# Esquematico_DIY.net
KiCad netlist of a schematic drawn in Altium Designer
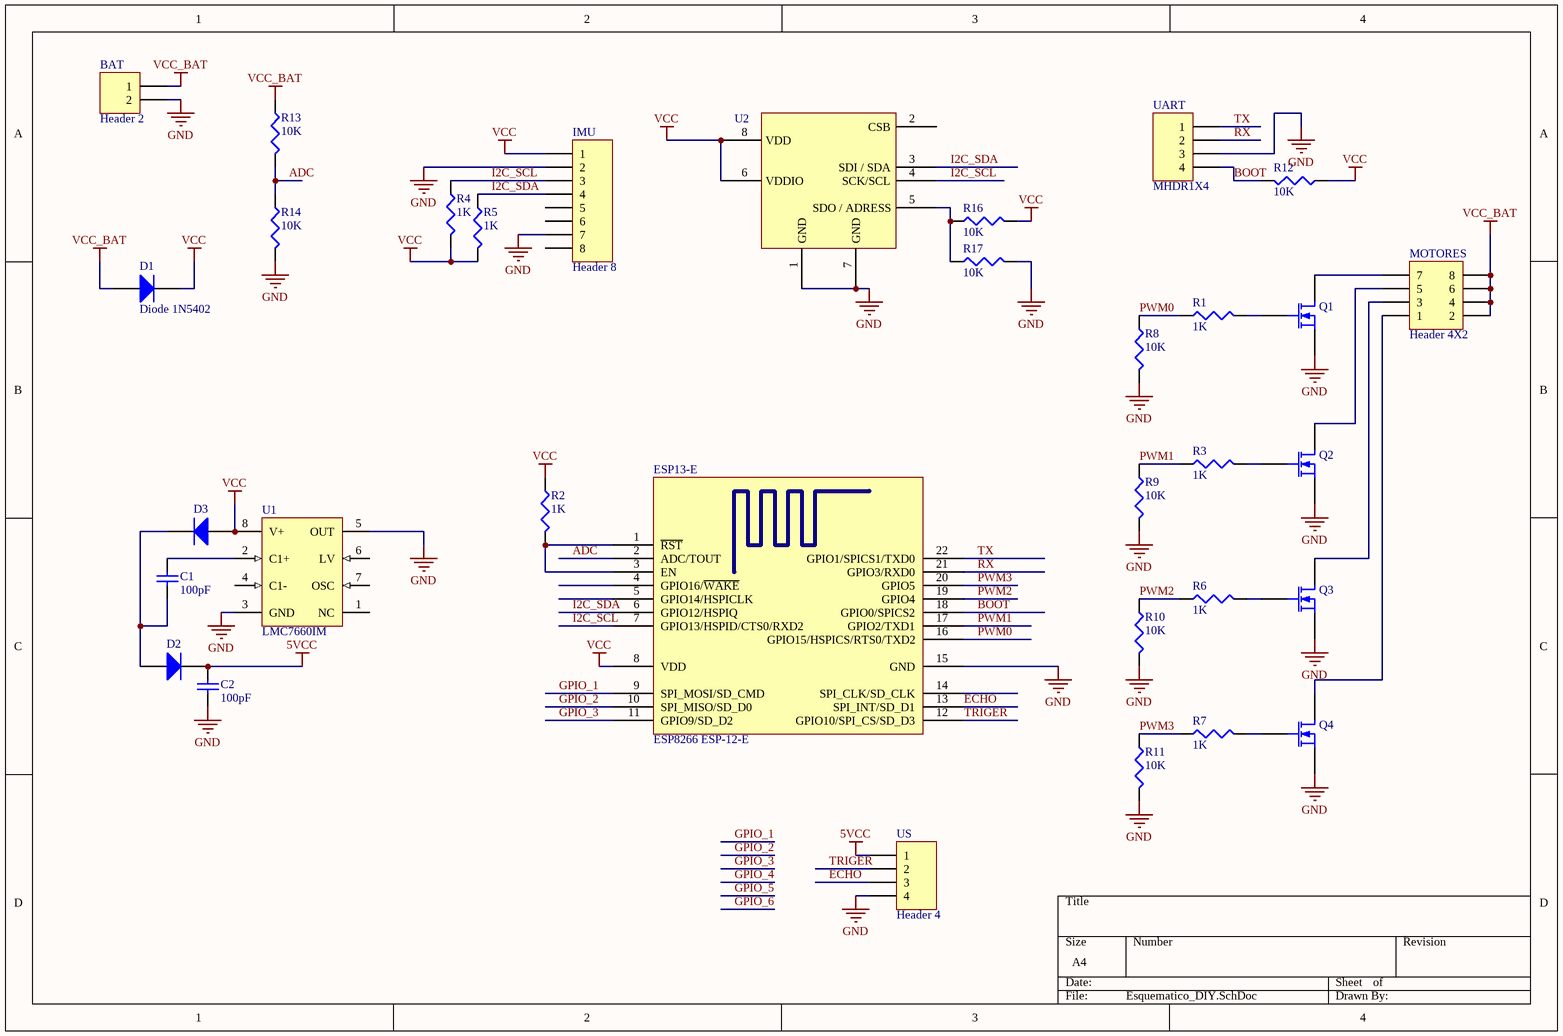
[diagram p0: Esquematico_DIY.SchDoc]

(export (version "E")
  (design (tool "Eeschema 10.0.6"))
  (components
    (comp (ref "BAT")
      (value "Header 2")
      (footprint "Miscellaneous Connectors:MHDR1X2")
      (description "Header, 2-Pin")
      (fields (field (name "PUBLISHER") "Altium Limited"))
      (libsource (lib "Miscellaneous Connectors") (part "Header 2"))
    )
    (comp (ref "C1")
      (value "100pF")
      (footprint "Miscellaneous Devices:C0805")
      (description "Capacitor")
      (fields (field (name "Comment") "Cap") (field (name "PUBLISHER") "Altium Limited"))
      (libsource (lib "Miscellaneous Devices") (part "Cap"))
    )
    (comp (ref "C2")
      (value "100pF")
      (footprint "Miscellaneous Devices:C0805")
      (description "Capacitor")
      (fields (field (name "Comment") "Cap") (field (name "PUBLISHER") "Altium Limited"))
      (libsource (lib "Miscellaneous Devices") (part "Cap"))
    )
    (comp (ref "D1")
      (value "Diode 1N5402")
      (footprint "DSO-C2/X2.3")
      (description "3 Amp General Purpose Rectifier")
      (fields (field (name "PUBLISHER") "Altium Limited"))
      (libsource (lib "Miscellaneous Devices") (part "Diode 1N5402"))
    )
    (comp (ref "D2")
      (value "Diode 1N5402")
      (footprint "DSO-C2/Z6.7")
      (description "3 Amp General Purpose Rectifier")
      (fields (field (name "PUBLISHER") "Altium Limited"))
      (libsource (lib "Miscellaneous Devices") (part "Diode 1N5402"))
    )
    (comp (ref "D3")
      (value "Diode 1N5402")
      (footprint "DSO-C2/Z6.7")
      (description "3 Amp General Purpose Rectifier")
      (fields (field (name "PUBLISHER") "Altium Limited"))
      (libsource (lib "Miscellaneous Devices") (part "Diode 1N5402"))
    )
    (comp (ref "ESP13-E")
      (value "ESP8266 ESP-12-E")
      (footprint "ESP8266:ESP8266 ESP-12-E B")
      (libsource (lib "ESP8266") (part "ESP8266 ESP-12-E"))
    )
    (comp (ref "IMU")
      (value "Header 8")
      (footprint "HDR1X8")
      (description "Header, 8-Pin")
      (fields (field (name "PUBLISHER") "Altium Limited"))
      (libsource (lib "Miscellaneous Connectors") (part "Header 8"))
    )
    (comp (ref "MOTORES")
      (value "Header 4X2")
      (footprint "HDR2X4")
      (description "Header, 4-Pin, Dual row")
      (fields (field (name "PUBLISHER") "Altium Limited"))
      (libsource (lib "Miscellaneous Connectors") (part "Header 4X2"))
    )
    (comp (ref "Q1")
      (value "MOSFET-N")
      (footprint "PBL - SMD Packages:SOT23-3")
      (description "N-Channel MOSFET")
      (fields (field (name "PUBLISHER") "Altium Limited"))
      (libsource (lib "Miscellaneous Devices") (part "MOSFET-N"))
    )
    (comp (ref "Q2")
      (value "MOSFET-N")
      (footprint "PBL - SMD Packages:SOT23-3")
      (description "N-Channel MOSFET")
      (fields (field (name "PUBLISHER") "Altium Limited"))
      (libsource (lib "Miscellaneous Devices") (part "MOSFET-N"))
    )
    (comp (ref "Q3")
      (value "MOSFET-N")
      (footprint "PBL - SMD Packages:SOT23-3")
      (description "N-Channel MOSFET")
      (fields (field (name "PUBLISHER") "Altium Limited"))
      (libsource (lib "Miscellaneous Devices") (part "MOSFET-N"))
    )
    (comp (ref "Q4")
      (value "MOSFET-N")
      (footprint "PBL - SMD Packages:SOT23-3")
      (description "N-Channel MOSFET")
      (fields (field (name "PUBLISHER") "Altium Limited"))
      (libsource (lib "Miscellaneous Devices") (part "MOSFET-N"))
    )
    (comp (ref "R1")
      (value "1K")
      (footprint "C0805")
      (description "Resistor")
      (fields (field (name "Comment") "Res3") (field (name "PUBLISHER") "Altium Limited"))
      (libsource (lib "Miscellaneous Devices") (part "Res3"))
    )
    (comp (ref "R2")
      (value "1K")
      (footprint "C0805")
      (description "Resistor")
      (fields (field (name "Comment") "Res3") (field (name "PUBLISHER") "Altium Limited"))
      (libsource (lib "Miscellaneous Devices") (part "Res3"))
    )
    (comp (ref "R3")
      (value "1K")
      (footprint "C0805")
      (description "Resistor")
      (fields (field (name "Comment") "Res3") (field (name "PUBLISHER") "Altium Limited"))
      (libsource (lib "Miscellaneous Devices") (part "Res3"))
    )
    (comp (ref "R4")
      (value "1K")
      (footprint "C1206")
      (description "Resistor")
      (fields (field (name "Comment") "Res3") (field (name "PUBLISHER") "Altium Limited"))
      (libsource (lib "Miscellaneous Devices") (part "Res3"))
    )
    (comp (ref "R5")
      (value "1K")
      (footprint "C1206")
      (description "Resistor")
      (fields (field (name "Comment") "Res3") (field (name "PUBLISHER") "Altium Limited"))
      (libsource (lib "Miscellaneous Devices") (part "Res3"))
    )
    (comp (ref "R6")
      (value "1K")
      (footprint "C0805")
      (description "Resistor")
      (fields (field (name "Comment") "Res3") (field (name "PUBLISHER") "Altium Limited"))
      (libsource (lib "Miscellaneous Devices") (part "Res3"))
    )
    (comp (ref "R7")
      (value "1K")
      (footprint "C0805")
      (description "Resistor")
      (fields (field (name "Comment") "Res3") (field (name "PUBLISHER") "Altium Limited"))
      (libsource (lib "Miscellaneous Devices") (part "Res3"))
    )
    (comp (ref "R8")
      (value "10K")
      (footprint "C0805")
      (description "Resistor")
      (fields (field (name "Comment") "Res3") (field (name "PUBLISHER") "Altium Limited"))
      (libsource (lib "Miscellaneous Devices") (part "Res3"))
    )
    (comp (ref "R9")
      (value "10K")
      (footprint "C0805")
      (description "Resistor")
      (fields (field (name "Comment") "Res3") (field (name "PUBLISHER") "Altium Limited"))
      (libsource (lib "Miscellaneous Devices") (part "Res3"))
    )
    (comp (ref "R10")
      (value "10K")
      (footprint "C0805")
      (description "Resistor")
      (fields (field (name "Comment") "Res3") (field (name "PUBLISHER") "Altium Limited"))
      (libsource (lib "Miscellaneous Devices") (part "Res3"))
    )
    (comp (ref "R11")
      (value "10K")
      (footprint "C0805")
      (description "Resistor")
      (fields (field (name "Comment") "Res3") (field (name "PUBLISHER") "Altium Limited"))
      (libsource (lib "Miscellaneous Devices") (part "Res3"))
    )
    (comp (ref "R12")
      (value "10K")
      (footprint "C1206")
      (description "Resistor")
      (fields (field (name "Comment") "Res3") (field (name "PUBLISHER") "Altium Limited"))
      (libsource (lib "Miscellaneous Devices") (part "Res3"))
    )
    (comp (ref "R13")
      (value "10K")
      (footprint "C0805")
      (description "Resistor")
      (fields (field (name "Comment") "Res3") (field (name "PUBLISHER") "Altium Limited"))
      (libsource (lib "Miscellaneous Devices") (part "Res3"))
    )
    (comp (ref "R14")
      (value "10K")
      (footprint "C0805")
      (description "Resistor")
      (fields (field (name "Comment") "Res3") (field (name "PUBLISHER") "Altium Limited"))
      (libsource (lib "Miscellaneous Devices") (part "Res3"))
    )
    (comp (ref "R16")
      (value "10K")
      (footprint "C0805")
      (description "Resistor")
      (fields (field (name "Comment") "Res3") (field (name "PUBLISHER") "Altium Limited"))
      (libsource (lib "Miscellaneous Devices") (part "Res3"))
    )
    (comp (ref "R17")
      (value "10K")
      (footprint "C0805")
      (description "Resistor")
      (fields (field (name "Comment") "Res3") (field (name "PUBLISHER") "Altium Limited"))
      (libsource (lib "Miscellaneous Devices") (part "Res3"))
    )
    (comp (ref "U1")
      (value "LMC7660IM")
      (footprint "M08A_N")
      (description "Switched Capacitor Voltage Converter, 8-pin Narrow SOIC")
      (fields
        (field (name "MANUFACTURER") "National Semiconductor")
        (field (name "PUBLISHER") "Altium Limited")
      )
      (libsource (lib "NSC Switch Caps") (part "LMC7660IM"))
    )
    (comp (ref "U2")
      (value "BMP280")
      (footprint "LGA-8_BMP280(Primary)")
      (description "Barometro")
      (libsource (lib "BMP280") (part "BMP280"))
    )
    (comp (ref "UART")
      (value "MHDR1X4")
      (footprint "MHDR1X4")
      (description "Header, 4-Pin")
      (fields (field (name "PUBLISHER") "Altium Limited"))
      (libsource (lib "Miscellaneous Connectors") (part "MHDR1X4"))
    )
    (comp (ref "US")
      (value "Header 4")
      (footprint "HDR1X4")
      (description "Header, 4-Pin")
      (fields (field (name "PUBLISHER") "Altium Limited"))
      (libsource (lib "Miscellaneous Connectors") (part "Header 4"))
    )
  )
  (nets
    (net (code "1") (name "/ADC") (class "Default")
      (node (ref "ESP13-E") (pin "2") (pinfunction "ADC/TOUT_2") (pintype "passive"))
      (node (ref "R13") (pin "2") (pinfunction "2_2") (pintype "passive"))
      (node (ref "R14") (pin "1") (pinfunction "1_1") (pintype "passive"))
    )
    (net (code "2") (name "/BOOT") (class "Default")
      (node (ref "ESP13-E") (pin "18") (pinfunction "GPIO0/SPICS2_18") (pintype "passive"))
      (node (ref "R12") (pin "2") (pinfunction "2_2") (pintype "passive"))
      (node (ref "UART") (pin "4") (pinfunction "4_4") (pintype "passive"))
    )
    (net (code "3") (name "/ECHO") (class "Default")
      (node (ref "ESP13-E") (pin "13") (pinfunction "SPI_INT/SD_D1_13") (pintype "passive"))
      (node (ref "US") (pin "3") (pinfunction "3_3") (pintype "passive"))
    )
    (net (code "4") (name "/GPIO_1") (class "Default")
      (node (ref "ESP13-E") (pin "9") (pinfunction "SPI_MOSI/SD_CMD_9") (pintype "passive"))
    )
    (net (code "5") (name "/GPIO_2") (class "Default")
      (node (ref "ESP13-E") (pin "10") (pinfunction "SPI_MISO/SD_D0_10") (pintype "passive"))
    )
    (net (code "6") (name "/GPIO_3") (class "Default")
      (node (ref "ESP13-E") (pin "11") (pinfunction "GPIO9/SD_D2_11") (pintype "passive"))
    )
    (net (code "10") (name "/I2C_SCL") (class "Default")
      (node (ref "ESP13-E") (pin "7") (pinfunction "GPIO13/HSPID/CTS0/RXD2_7") (pintype "passive"))
      (node (ref "IMU") (pin "3") (pinfunction "3_3") (pintype "passive"))
      (node (ref "R4") (pin "1") (pinfunction "1_1") (pintype "passive"))
      (node (ref "U2") (pin "4") (pinfunction "SCK/SCL_4") (pintype "passive"))
    )
    (net (code "11") (name "/I2C_SDA") (class "Default")
      (node (ref "ESP13-E") (pin "6") (pinfunction "GPIO12/HSPIQ_6") (pintype "passive"))
      (node (ref "IMU") (pin "4") (pinfunction "4_4") (pintype "passive"))
      (node (ref "R5") (pin "1") (pinfunction "1_1") (pintype "passive"))
      (node (ref "U2") (pin "3") (pinfunction "SDI_/_SDA_3") (pintype "passive"))
    )
    (net (code "12") (name "/PWM0") (class "Default")
      (node (ref "ESP13-E") (pin "16") (pinfunction "GPIO15/HSPICS/RTS0/TXD2_16") (pintype "passive"))
      (node (ref "R1") (pin "1") (pinfunction "1_1") (pintype "passive"))
      (node (ref "R8") (pin "1") (pinfunction "1_1") (pintype "passive"))
    )
    (net (code "13") (name "/PWM1") (class "Default")
      (node (ref "ESP13-E") (pin "17") (pinfunction "GPIO2/TXD1_17") (pintype "passive"))
      (node (ref "R3") (pin "1") (pinfunction "1_1") (pintype "passive"))
      (node (ref "R9") (pin "1") (pinfunction "1_1") (pintype "passive"))
    )
    (net (code "14") (name "/PWM2") (class "Default")
      (node (ref "ESP13-E") (pin "19") (pinfunction "GPIO4_19") (pintype "passive"))
      (node (ref "R10") (pin "1") (pinfunction "1_1") (pintype "passive"))
      (node (ref "R6") (pin "1") (pinfunction "1_1") (pintype "passive"))
    )
    (net (code "15") (name "/PWM3") (class "Default")
      (node (ref "ESP13-E") (pin "20") (pinfunction "GPIO5_20") (pintype "passive"))
      (node (ref "R11") (pin "1") (pinfunction "1_1") (pintype "passive"))
      (node (ref "R7") (pin "1") (pinfunction "1_1") (pintype "passive"))
    )
    (net (code "16") (name "/RX") (class "Default")
      (node (ref "ESP13-E") (pin "21") (pinfunction "GPIO3/RXD0_21") (pintype "passive"))
      (node (ref "UART") (pin "2") (pinfunction "2_2") (pintype "passive"))
    )
    (net (code "17") (name "/TRIGER") (class "Default")
      (node (ref "ESP13-E") (pin "12") (pinfunction "GPIO10/SPI_CS/SD_D3_12") (pintype "passive"))
      (node (ref "US") (pin "2") (pinfunction "2_2") (pintype "passive"))
    )
    (net (code "18") (name "/TX") (class "Default")
      (node (ref "ESP13-E") (pin "22") (pinfunction "GPIO1/SPICS1/TXD0_22") (pintype "passive"))
      (node (ref "UART") (pin "1") (pinfunction "1_1") (pintype "passive"))
    )
    (net (code "19") (name "5VCC") (class "Default")
      (node (ref "C2") (pin "2") (pinfunction "2_2") (pintype "passive"))
      (node (ref "D2") (pin "2") (pinfunction "K_2") (pintype "passive"))
      (node (ref "US") (pin "1") (pinfunction "1_1") (pintype "passive"))
    )
    (net (code "20") (name "GND") (class "Default")
      (node (ref "BAT") (pin "2") (pinfunction "2_2") (pintype "passive"))
      (node (ref "C2") (pin "1") (pinfunction "1_1") (pintype "passive"))
      (node (ref "ESP13-E") (pin "15") (pinfunction "GND_15") (pintype "passive"))
      (node (ref "IMU") (pin "2") (pinfunction "2_2") (pintype "passive"))
      (node (ref "IMU") (pin "7") (pinfunction "7_7") (pintype "passive"))
      (node (ref "Q1") (pin "3") (pinfunction "S_3") (pintype "passive"))
      (node (ref "Q2") (pin "3") (pinfunction "S_3") (pintype "passive"))
      (node (ref "Q3") (pin "3") (pinfunction "S_3") (pintype "passive"))
      (node (ref "Q4") (pin "3") (pinfunction "S_3") (pintype "passive"))
      (node (ref "R10") (pin "2") (pinfunction "2_2") (pintype "passive"))
      (node (ref "R11") (pin "2") (pinfunction "2_2") (pintype "passive"))
      (node (ref "R14") (pin "2") (pinfunction "2_2") (pintype "passive"))
      (node (ref "R17") (pin "2") (pinfunction "2_2") (pintype "passive"))
      (node (ref "R8") (pin "2") (pinfunction "2_2") (pintype "passive"))
      (node (ref "R9") (pin "2") (pinfunction "2_2") (pintype "passive"))
      (node (ref "U1") (pin "3") (pinfunction "GND_3") (pintype "power_in"))
      (node (ref "U1") (pin "5") (pinfunction "OUT_5") (pintype "power_in"))
      (node (ref "U2") (pin "1") (pinfunction "GND_1") (pintype "passive"))
      (node (ref "U2") (pin "7") (pinfunction "GND_7") (pintype "passive"))
      (node (ref "UART") (pin "3") (pinfunction "3_3") (pintype "passive"))
      (node (ref "US") (pin "4") (pinfunction "4_4") (pintype "passive"))
    )
    (net (code "21") (name "Net-(D2-A)") (class "Default")
      (node (ref "C1") (pin "2") (pinfunction "2_2") (pintype "passive"))
      (node (ref "D2") (pin "1") (pinfunction "A_1") (pintype "passive"))
      (node (ref "D3") (pin "2") (pinfunction "K_2") (pintype "passive"))
    )
    (net (code "22") (name "Net-(ESP13-E-EN)") (class "Default")
      (node (ref "ESP13-E") (pin "1") (pinfunction "~{RST}_1") (pintype "passive"))
      (node (ref "ESP13-E") (pin "3") (pinfunction "EN_3") (pintype "passive"))
      (node (ref "R2") (pin "2") (pinfunction "2_2") (pintype "passive"))
    )
    (net (code "23") (name "Net-(Q1-D)") (class "Default")
      (node (ref "MOTORES") (pin "7") (pinfunction "7_7") (pintype "passive"))
      (node (ref "Q1") (pin "1") (pinfunction "D_1") (pintype "passive"))
    )
    (net (code "24") (name "Net-(Q1-G)") (class "Default")
      (node (ref "Q1") (pin "2") (pinfunction "G_2") (pintype "passive"))
      (node (ref "R1") (pin "2") (pinfunction "2_2") (pintype "passive"))
    )
    (net (code "25") (name "Net-(Q2-D)") (class "Default")
      (node (ref "MOTORES") (pin "5") (pinfunction "5_5") (pintype "passive"))
      (node (ref "Q2") (pin "1") (pinfunction "D_1") (pintype "passive"))
    )
    (net (code "26") (name "Net-(Q2-G)") (class "Default")
      (node (ref "Q2") (pin "2") (pinfunction "G_2") (pintype "passive"))
      (node (ref "R3") (pin "2") (pinfunction "2_2") (pintype "passive"))
    )
    (net (code "27") (name "Net-(Q3-D)") (class "Default")
      (node (ref "MOTORES") (pin "3") (pinfunction "3_3") (pintype "passive"))
      (node (ref "Q3") (pin "1") (pinfunction "D_1") (pintype "passive"))
    )
    (net (code "28") (name "Net-(Q3-G)") (class "Default")
      (node (ref "Q3") (pin "2") (pinfunction "G_2") (pintype "passive"))
      (node (ref "R6") (pin "2") (pinfunction "2_2") (pintype "passive"))
    )
    (net (code "29") (name "Net-(Q4-D)") (class "Default")
      (node (ref "MOTORES") (pin "1") (pinfunction "1_1") (pintype "passive"))
      (node (ref "Q4") (pin "1") (pinfunction "D_1") (pintype "passive"))
    )
    (net (code "30") (name "Net-(Q4-G)") (class "Default")
      (node (ref "Q4") (pin "2") (pinfunction "G_2") (pintype "passive"))
      (node (ref "R7") (pin "2") (pinfunction "2_2") (pintype "passive"))
    )
    (net (code "31") (name "Net-(U1-C1+)") (class "Default")
      (node (ref "C1") (pin "1") (pinfunction "1_1") (pintype "passive"))
      (node (ref "U1") (pin "2") (pinfunction "C1+_2") (pintype "input"))
    )
    (net (code "32") (name "Net-(U2-SDO_{slash}_ADRESS)") (class "Default")
      (node (ref "R16") (pin "1") (pinfunction "1_1") (pintype "passive"))
      (node (ref "R17") (pin "1") (pinfunction "1_1") (pintype "passive"))
      (node (ref "U2") (pin "5") (pinfunction "SDO_/_ADRESS_5") (pintype "passive"))
    )
    (net (code "33") (name "VCC") (class "Default")
      (node (ref "D1") (pin "2") (pinfunction "K_2") (pintype "passive"))
      (node (ref "D3") (pin "1") (pinfunction "A_1") (pintype "passive"))
      (node (ref "ESP13-E") (pin "8") (pinfunction "VDD_8") (pintype "passive"))
      (node (ref "IMU") (pin "1") (pinfunction "1_1") (pintype "passive"))
      (node (ref "R12") (pin "1") (pinfunction "1_1") (pintype "passive"))
      (node (ref "R16") (pin "2") (pinfunction "2_2") (pintype "passive"))
      (node (ref "R2") (pin "1") (pinfunction "1_1") (pintype "passive"))
      (node (ref "R4") (pin "2") (pinfunction "2_2") (pintype "passive"))
      (node (ref "R5") (pin "2") (pinfunction "2_2") (pintype "passive"))
      (node (ref "U1") (pin "8") (pinfunction "V+_8") (pintype "power_in"))
      (node (ref "U2") (pin "6") (pinfunction "VDDIO_6") (pintype "passive"))
      (node (ref "U2") (pin "8") (pinfunction "VDD_8") (pintype "passive"))
    )
    (net (code "34") (name "VCC_BAT") (class "Default")
      (node (ref "BAT") (pin "1") (pinfunction "1_1") (pintype "passive"))
      (node (ref "D1") (pin "1") (pinfunction "A_1") (pintype "passive"))
      (node (ref "MOTORES") (pin "2") (pinfunction "2_2") (pintype "passive"))
      (node (ref "MOTORES") (pin "4") (pinfunction "4_4") (pintype "passive"))
      (node (ref "MOTORES") (pin "6") (pinfunction "6_6") (pintype "passive"))
      (node (ref "MOTORES") (pin "8") (pinfunction "8_8") (pintype "passive"))
      (node (ref "R13") (pin "1") (pinfunction "1_1") (pintype "passive"))
    )
    (net (code "35") (name "unconnected-(ESP13-E-GPIO14{slash}HSPICLK-Pad5)") (class "Default")
      (node (ref "ESP13-E") (pin "5") (pinfunction "GPIO14/HSPICLK_5") (pintype "passive"))
    )
    (net (code "36") (name "unconnected-(ESP13-E-GPIO16{slash}~{WAKE}-Pad4)") (class "Default")
      (node (ref "ESP13-E") (pin "4") (pinfunction "GPIO16/~{WAKE}_4") (pintype "passive"))
    )
    (net (code "37") (name "unconnected-(ESP13-E-SPI_CLK{slash}SD_CLK-Pad14)") (class "Default")
      (node (ref "ESP13-E") (pin "14") (pinfunction "SPI_CLK/SD_CLK_14") (pintype "passive"))
    )
    (net (code "38") (name "unconnected-(IMU-Pad5)") (class "Default")
      (node (ref "IMU") (pin "5") (pinfunction "5_5") (pintype "passive"))
    )
    (net (code "39") (name "unconnected-(IMU-Pad6)") (class "Default")
      (node (ref "IMU") (pin "6") (pinfunction "6_6") (pintype "passive"))
    )
    (net (code "40") (name "unconnected-(IMU-Pad8)") (class "Default")
      (node (ref "IMU") (pin "8") (pinfunction "8_8") (pintype "passive"))
    )
    (net (code "41") (name "unconnected-(U1-C1--Pad4)") (class "Default")
      (node (ref "U1") (pin "4") (pinfunction "C1-_4") (pintype "input"))
    )
    (net (code "42") (name "unconnected-(U1-LV-Pad6)") (class "Default")
      (node (ref "U1") (pin "6") (pinfunction "LV_6") (pintype "input"))
    )
    (net (code "43") (name "unconnected-(U1-NC-Pad1)") (class "Default")
      (node (ref "U1") (pin "1") (pinfunction "NC_1") (pintype "passive"))
    )
    (net (code "44") (name "unconnected-(U1-OSC-Pad7)") (class "Default")
      (node (ref "U1") (pin "7") (pinfunction "OSC_7") (pintype "input"))
    )
    (net (code "45") (name "unconnected-(U2-CSB-Pad2)") (class "Default")
      (node (ref "U2") (pin "2") (pinfunction "CSB_2") (pintype "passive"))
    )
  )
)
